# attiny85.net
KiCad netlist of a schematic drawn in EAGLE
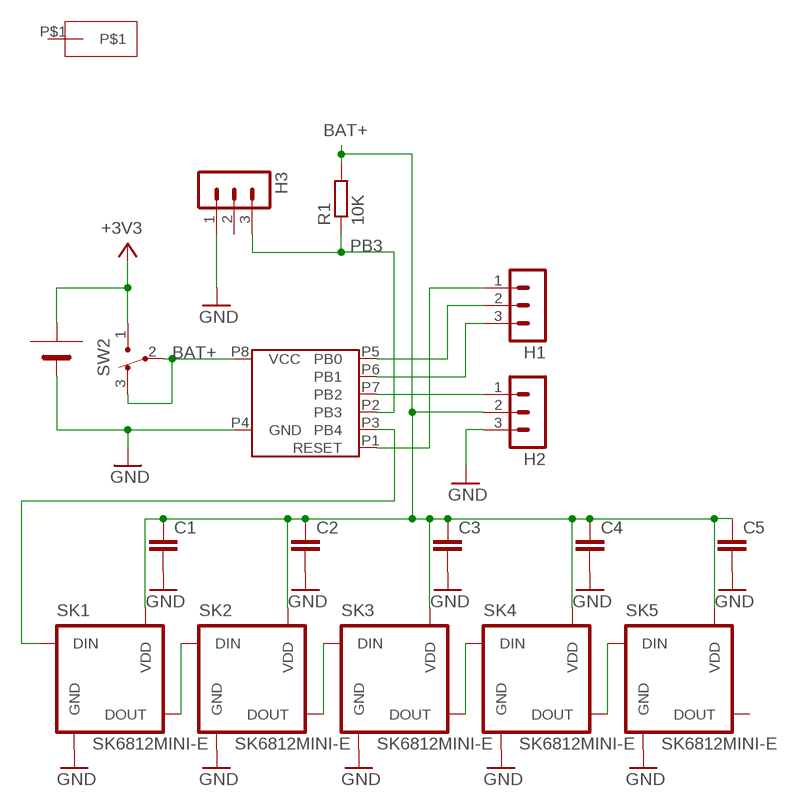
[diagram p0: schematic, sheet 1]

(export (version "E")
  (design (tool "Eeschema 10.0.6"))
  (components
    (comp (ref "ATTINY85-1")
      (value "ATTINY85")
      (footprint "eagle-import:ATTINY85-20SUR")
      (libsource (lib "eagle-import") (part "ATTINY85SOP8"))
    )
    (comp (ref "BAT1")
      (value "BAT-CR2032")
      (footprint "eagle-import:BAT-CR2032-1")
      (libsource (lib "eagle-import") (part "BAT-CR2032"))
    )
    (comp (ref "C1")
      (value "C-EUC2012")
      (footprint "eagle-import:C2012")
      (libsource (lib "eagle-import") (part "C-EUC2012"))
    )
    (comp (ref "C2")
      (value "C-EUC2012")
      (footprint "eagle-import:C2012")
      (libsource (lib "eagle-import") (part "C-EUC2012"))
    )
    (comp (ref "C3")
      (value "C-EUC2012")
      (footprint "eagle-import:C2012")
      (libsource (lib "eagle-import") (part "C-EUC2012"))
    )
    (comp (ref "C4")
      (value "C-EUC2012")
      (footprint "eagle-import:C2012")
      (libsource (lib "eagle-import") (part "C-EUC2012"))
    )
    (comp (ref "C5")
      (value "C-EUC2012")
      (footprint "eagle-import:C2012")
      (libsource (lib "eagle-import") (part "C-EUC2012"))
    )
    (comp (ref "H1")
      (value "PINHEAD-MA03-1SMD")
      (footprint "eagle-import:PINHEAD-MA03-2")
      (libsource (lib "eagle-import") (part "PINHEAD-MA03-1SMD"))
    )
    (comp (ref "H2")
      (value "PINHEAD-MA03-1SMD")
      (footprint "eagle-import:PINHEAD-MA03-2")
      (libsource (lib "eagle-import") (part "PINHEAD-MA03-1SMD"))
    )
    (comp (ref "H3")
      (value "PINHEAD-MA03-1")
      (footprint "eagle-import:PINHEAD-MA03-1")
      (libsource (lib "eagle-import") (part "PINHEAD-MA03-1"))
    )
    (comp (ref "PAD33")
      (value "PAD12X4")
      (footprint "eagle-import:PAD-12X4")
      (libsource (lib "eagle-import") (part "PAD12X4"))
    )
    (comp (ref "R1")
      (value "10K")
      (footprint "eagle-import:M3216")
      (libsource (lib "eagle-import") (part "R-EU_M3216"))
    )
    (comp (ref "SK1")
      (value "SK6812MINI-E")
      (footprint "eagle-import:SK6812MINI-E")
      (libsource (lib "eagle-import") (part "SK6812MINI-E"))
    )
    (comp (ref "SK2")
      (value "SK6812MINI-E")
      (footprint "eagle-import:SK6812MINI-E")
      (libsource (lib "eagle-import") (part "SK6812MINI-E"))
    )
    (comp (ref "SK3")
      (value "SK6812MINI-E")
      (footprint "eagle-import:SK6812MINI-E")
      (libsource (lib "eagle-import") (part "SK6812MINI-E"))
    )
    (comp (ref "SK4")
      (value "SK6812MINI-E")
      (footprint "eagle-import:SK6812MINI-E")
      (libsource (lib "eagle-import") (part "SK6812MINI-E"))
    )
    (comp (ref "SK5")
      (value "SK6812MINI-E")
      (footprint "eagle-import:SK6812MINI-E")
      (libsource (lib "eagle-import") (part "SK6812MINI-E"))
    )
    (comp (ref "SW2")
      (value "POWER")
      (footprint "eagle-import:SW3-1")
      (fields (field (name "MF") "HiLetgo"))
      (libsource (lib "eagle-import") (part "SW3-1"))
    )
  )
  (nets
    (net (code "1") (name "+3V3") (class "Default")
      (node (ref "BAT1") (pin "BAT+") (pinfunction "BAT+_BAT+") (pintype "bidirectional"))
      (node (ref "SW2") (pin "1") (pinfunction "1_1") (pintype "passive"))
    )
    (net (code "2") (name "/BAT+") (class "Default")
      (node (ref "ATTINY85-1") (pin "P8") (pinfunction "VCC_P8") (pintype "bidirectional"))
      (node (ref "C1") (pin "1") (pinfunction "1_1") (pintype "passive"))
      (node (ref "C2") (pin "1") (pinfunction "1_1") (pintype "passive"))
      (node (ref "C3") (pin "1") (pinfunction "1_1") (pintype "passive"))
      (node (ref "C4") (pin "1") (pinfunction "1_1") (pintype "passive"))
      (node (ref "C5") (pin "1") (pinfunction "1_1") (pintype "passive"))
      (node (ref "H2") (pin "2") (pinfunction "2_2") (pintype "passive"))
      (node (ref "R1") (pin "2") (pinfunction "2_2") (pintype "passive"))
      (node (ref "SK1") (pin "VDD") (pinfunction "VDD_VDD") (pintype "bidirectional"))
      (node (ref "SK2") (pin "VDD") (pinfunction "VDD_VDD") (pintype "bidirectional"))
      (node (ref "SK3") (pin "VDD") (pinfunction "VDD_VDD") (pintype "bidirectional"))
      (node (ref "SK4") (pin "VDD") (pinfunction "VDD_VDD") (pintype "bidirectional"))
      (node (ref "SK5") (pin "VDD") (pinfunction "VDD_VDD") (pintype "bidirectional"))
      (node (ref "SW2") (pin "2") (pinfunction "2_2") (pintype "passive"))
      (node (ref "SW2") (pin "3") (pinfunction "3_3") (pintype "passive"))
    )
    (net (code "3") (name "/PB3") (class "Default")
      (node (ref "ATTINY85-1") (pin "P2") (pinfunction "PB3_P2") (pintype "bidirectional"))
      (node (ref "H3") (pin "3") (pinfunction "3_3") (pintype "passive"))
      (node (ref "R1") (pin "1") (pinfunction "1_1") (pintype "passive"))
    )
    (net (code "4") (name "GND") (class "Default")
      (node (ref "ATTINY85-1") (pin "P4") (pinfunction "GND_P4") (pintype "bidirectional"))
      (node (ref "BAT1") (pin "BAT-") (pinfunction "P$1_BAT-") (pintype "bidirectional"))
      (node (ref "C1") (pin "2") (pinfunction "2_2") (pintype "passive"))
      (node (ref "C2") (pin "2") (pinfunction "2_2") (pintype "passive"))
      (node (ref "C3") (pin "2") (pinfunction "2_2") (pintype "passive"))
      (node (ref "C4") (pin "2") (pinfunction "2_2") (pintype "passive"))
      (node (ref "C5") (pin "2") (pinfunction "2_2") (pintype "passive"))
      (node (ref "H2") (pin "3") (pinfunction "3_3") (pintype "passive"))
      (node (ref "H3") (pin "1") (pinfunction "1_1") (pintype "passive"))
      (node (ref "SK1") (pin "GND") (pinfunction "GND_GND") (pintype "bidirectional"))
      (node (ref "SK2") (pin "GND") (pinfunction "GND_GND") (pintype "bidirectional"))
      (node (ref "SK3") (pin "GND") (pinfunction "GND_GND") (pintype "bidirectional"))
      (node (ref "SK4") (pin "GND") (pinfunction "GND_GND") (pintype "bidirectional"))
      (node (ref "SK5") (pin "GND") (pinfunction "GND_GND") (pintype "bidirectional"))
    )
    (net (code "5") (name "Net-(ATTINY85-1-PB0)") (class "Default")
      (node (ref "ATTINY85-1") (pin "P5") (pinfunction "PB0_P5") (pintype "bidirectional"))
      (node (ref "H1") (pin "2") (pinfunction "2_2") (pintype "passive"))
    )
    (net (code "6") (name "Net-(ATTINY85-1-PB1)") (class "Default")
      (node (ref "ATTINY85-1") (pin "P6") (pinfunction "PB1_P6") (pintype "bidirectional"))
      (node (ref "H1") (pin "3") (pinfunction "3_3") (pintype "passive"))
    )
    (net (code "7") (name "Net-(ATTINY85-1-PB2)") (class "Default")
      (node (ref "ATTINY85-1") (pin "P7") (pinfunction "PB2_P7") (pintype "bidirectional"))
      (node (ref "H2") (pin "1") (pinfunction "1_1") (pintype "passive"))
    )
    (net (code "8") (name "Net-(ATTINY85-1-PB4)") (class "Default")
      (node (ref "ATTINY85-1") (pin "P3") (pinfunction "PB4_P3") (pintype "bidirectional"))
      (node (ref "SK1") (pin "DIN") (pinfunction "DIN_DIN") (pintype "input"))
    )
    (net (code "9") (name "Net-(ATTINY85-1-RESET)") (class "Default")
      (node (ref "ATTINY85-1") (pin "P1") (pinfunction "RESET_P1") (pintype "bidirectional"))
      (node (ref "H1") (pin "1") (pinfunction "1_1") (pintype "passive"))
    )
    (net (code "10") (name "Net-(SK1-PadDOUT)") (class "Default")
      (node (ref "SK1") (pin "DOUT") (pinfunction "DOUT_DOUT") (pintype "output"))
      (node (ref "SK2") (pin "DIN") (pinfunction "DIN_DIN") (pintype "input"))
    )
    (net (code "11") (name "Net-(SK2-PadDOUT)") (class "Default")
      (node (ref "SK2") (pin "DOUT") (pinfunction "DOUT_DOUT") (pintype "output"))
      (node (ref "SK3") (pin "DIN") (pinfunction "DIN_DIN") (pintype "input"))
    )
    (net (code "12") (name "Net-(SK3-PadDOUT)") (class "Default")
      (node (ref "SK3") (pin "DOUT") (pinfunction "DOUT_DOUT") (pintype "output"))
      (node (ref "SK4") (pin "DIN") (pinfunction "DIN_DIN") (pintype "input"))
    )
    (net (code "13") (name "Net-(SK4-PadDOUT)") (class "Default")
      (node (ref "SK4") (pin "DOUT") (pinfunction "DOUT_DOUT") (pintype "output"))
      (node (ref "SK5") (pin "DIN") (pinfunction "DIN_DIN") (pintype "input"))
    )
    (net (code "14") (name "unconnected-(H3-Pad2)") (class "Default")
      (node (ref "H3") (pin "2") (pinfunction "2_2") (pintype "passive"))
    )
    (net (code "15") (name "unconnected-(PAD33-PadP$1)") (class "Default")
      (node (ref "PAD33") (pin "P$1") (pinfunction "P$1_P$1") (pintype "bidirectional"))
    )
    (net (code "16") (name "unconnected-(SK5-PadDOUT)") (class "Default")
      (node (ref "SK5") (pin "DOUT") (pinfunction "DOUT_DOUT") (pintype "output"))
    )
  )
)
